# bh_carrier_0_beta.net
KiCad netlist of a schematic drawn in Altium Designer
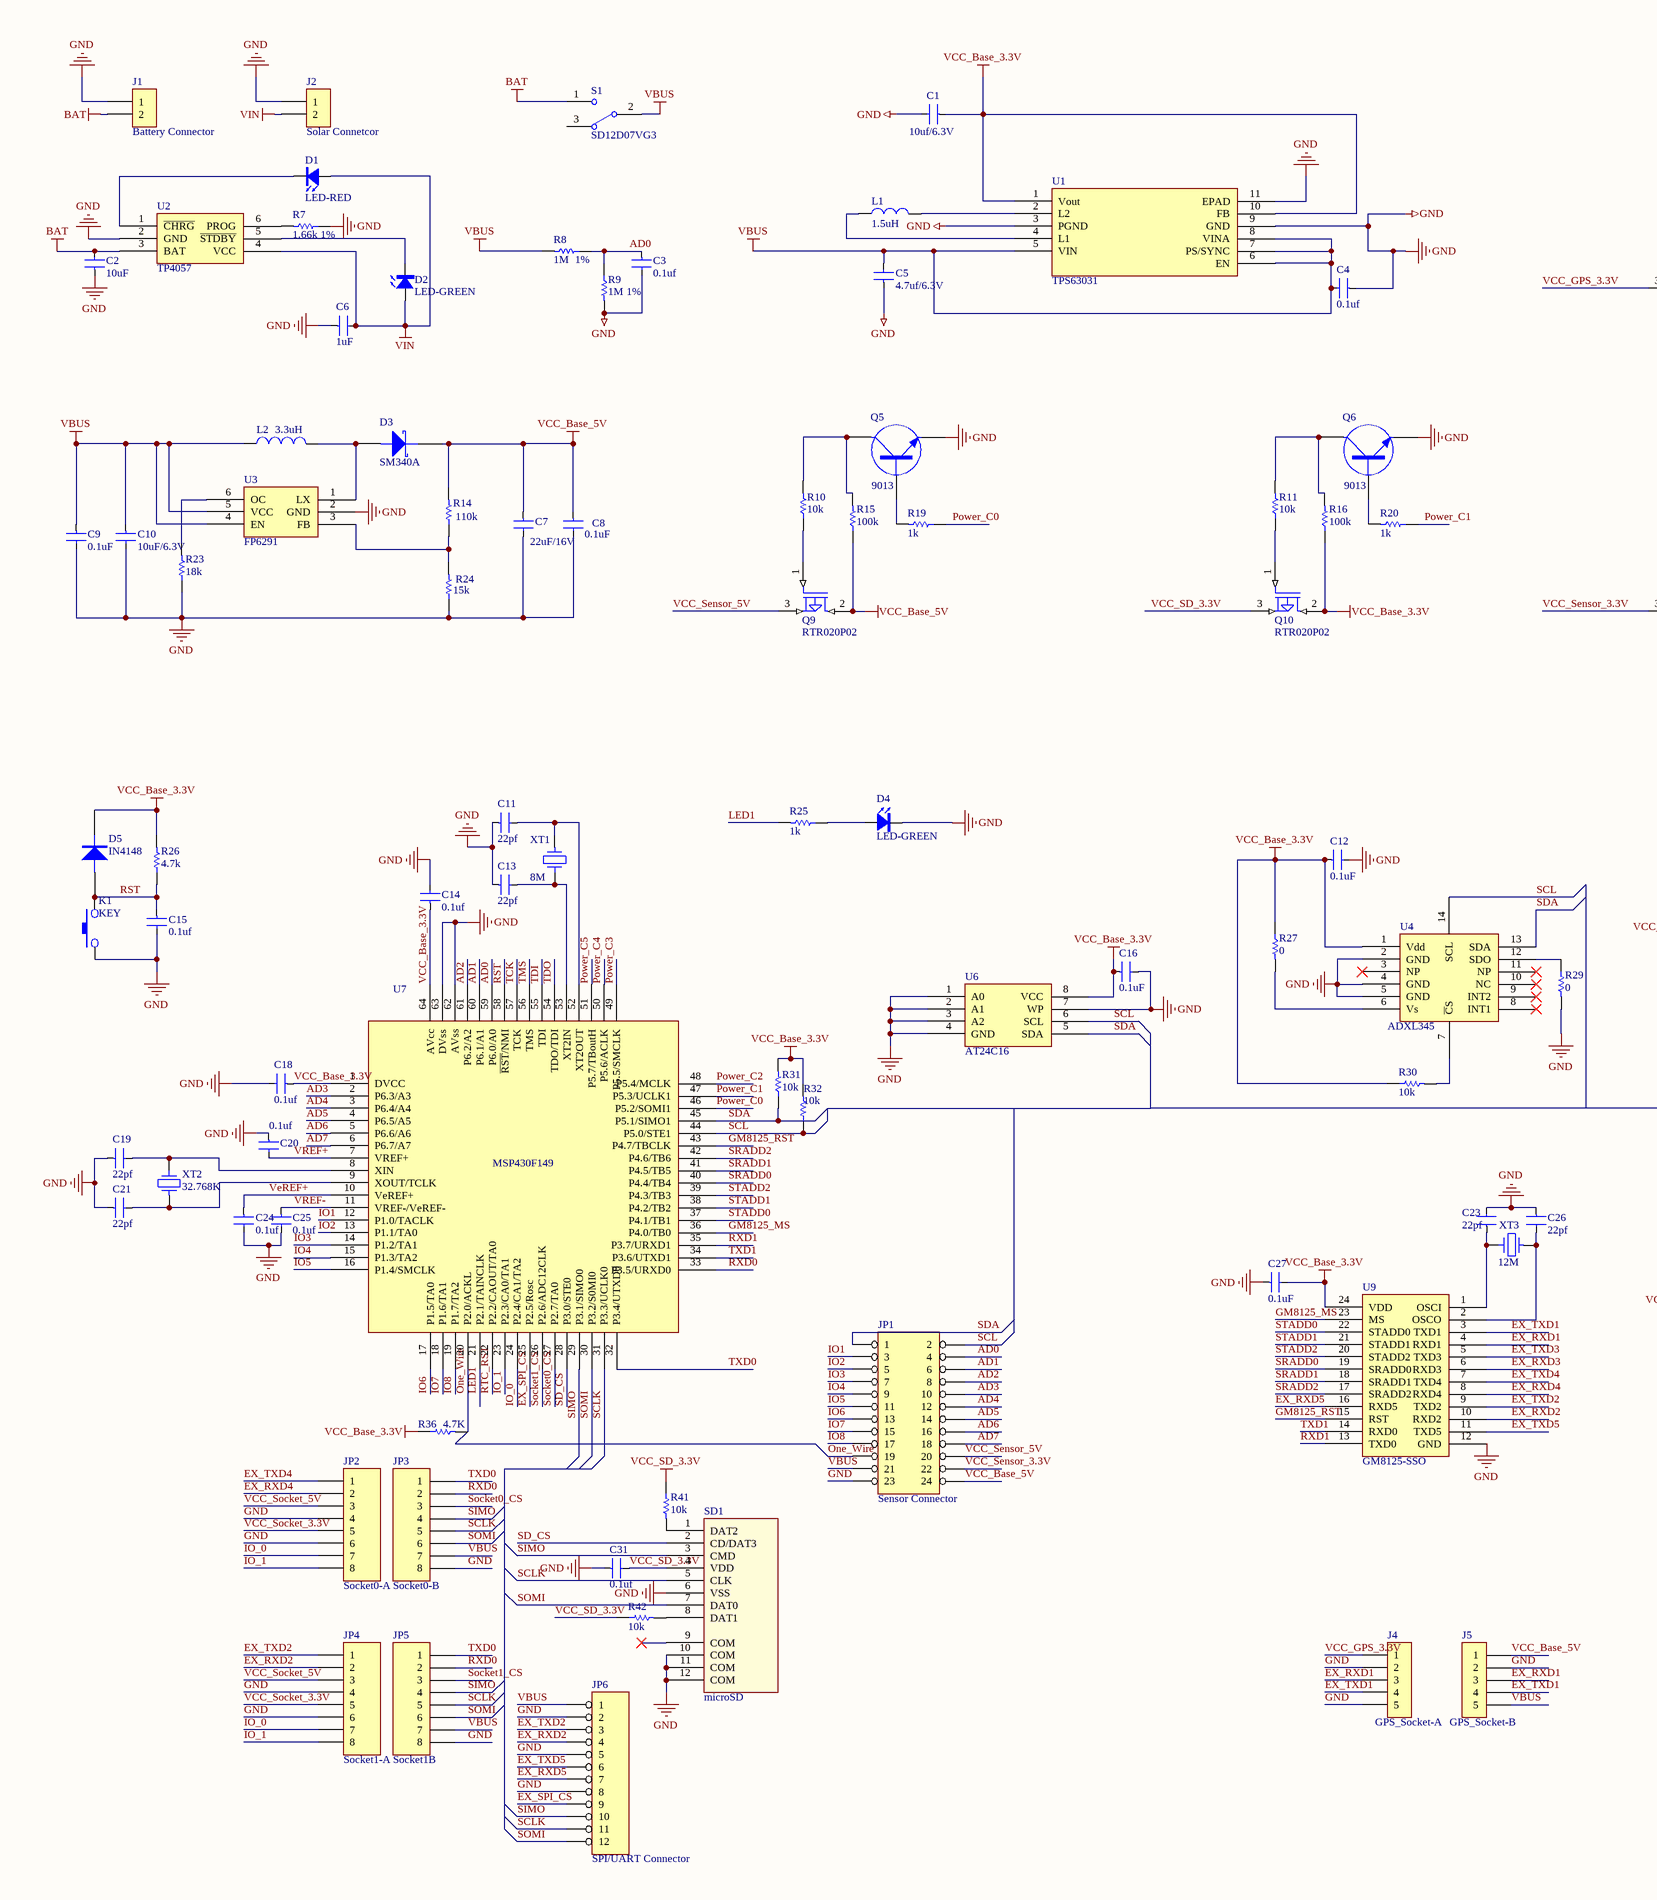
[diagram p0: bh_carrier_0_beta.SchDoc, left]
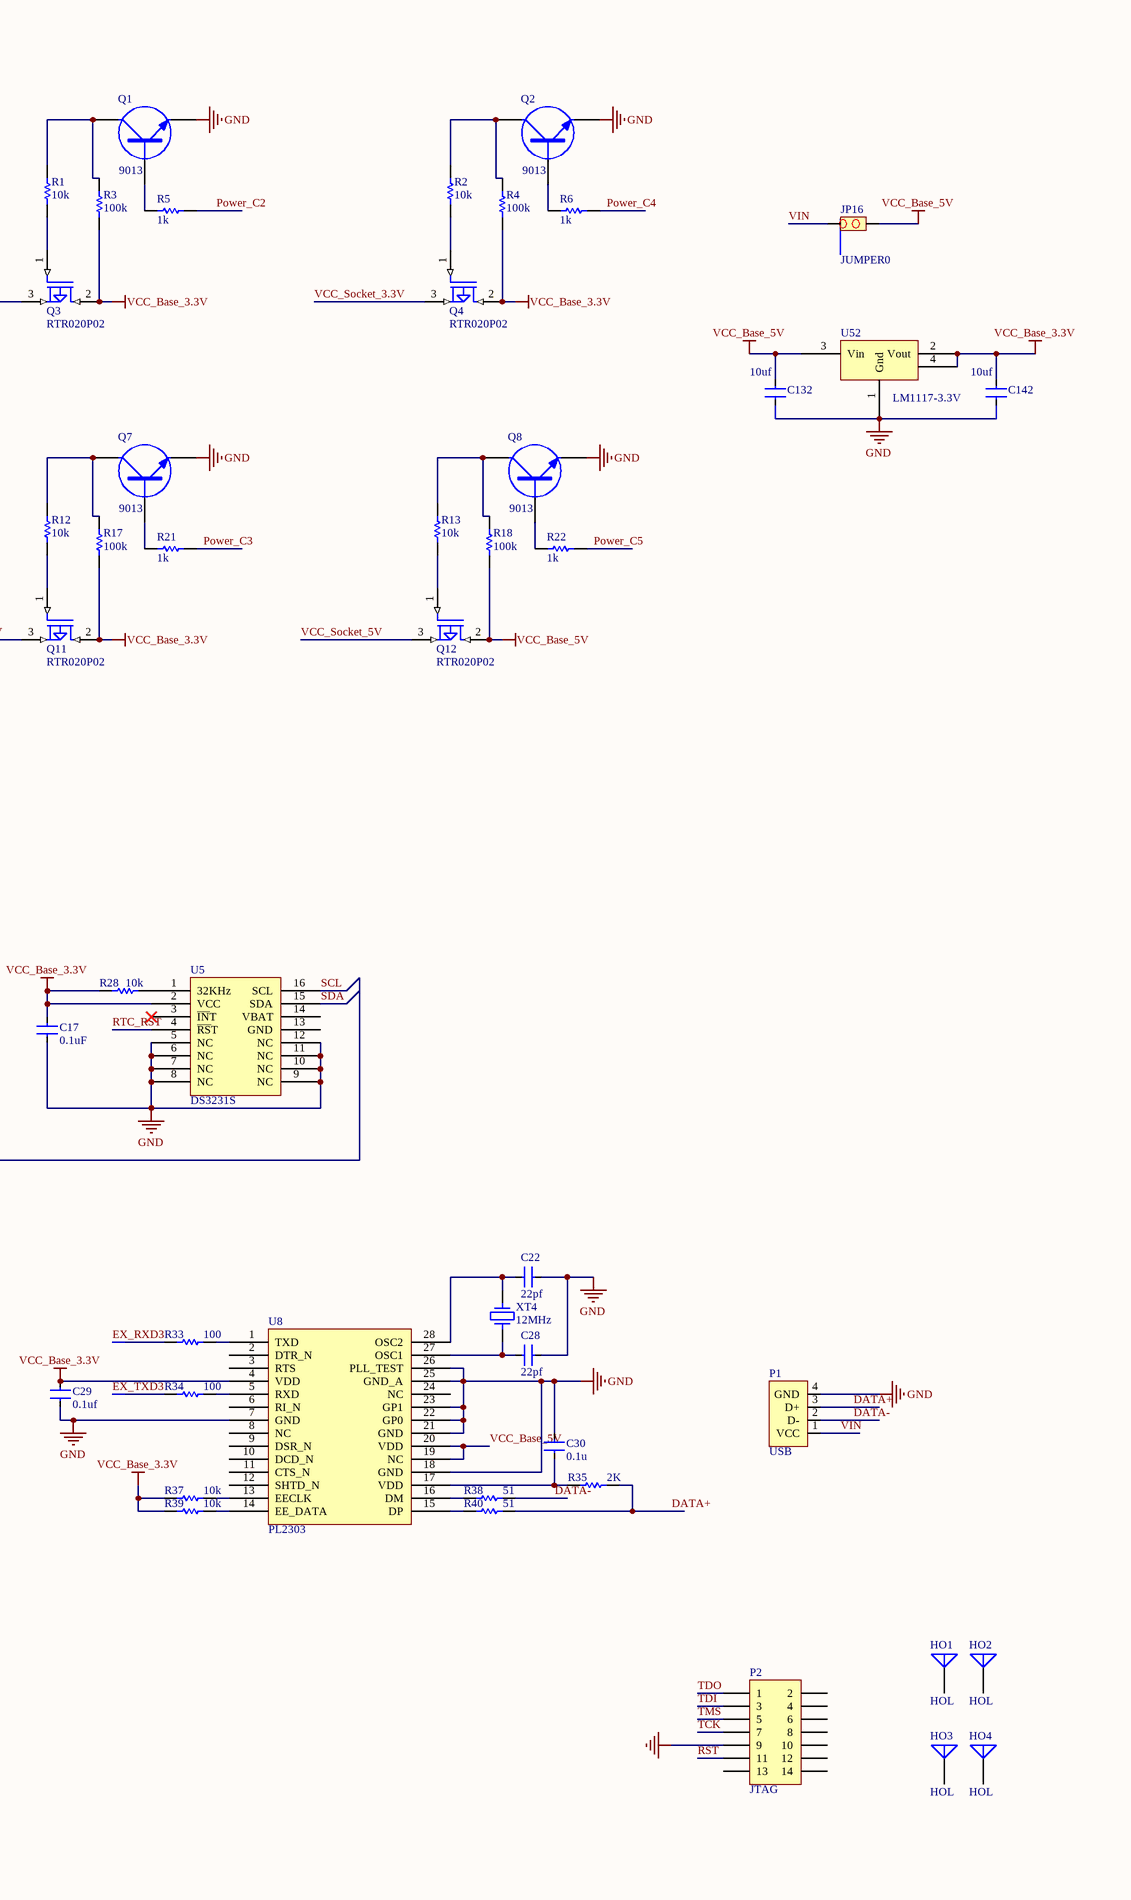
[diagram p1: bh_carrier_0_beta.SchDoc, right]

(export (version "E")
  (design (tool "Eeschema 10.0.6"))
  (components
    (comp (ref "C1")
      (value "10uf/6.3V")
      (footprint "C0603")
      (description "SMD-CAP")
      (libsource (lib "5D_USED_DEVICE") (part "CAP-SMD"))
    )
    (comp (ref "C2")
      (value "10uF")
      (footprint "C0603")
      (description "SMD-CAP")
      (libsource (lib "5D_DEVICE") (part "CAP-SMD"))
    )
    (comp (ref "C3")
      (value "0.1uf")
      (footprint "C0603")
      (description "SMD-CAP")
      (libsource (lib "5D_USED_DEVICE") (part "CAP-SMD"))
    )
    (comp (ref "C4")
      (value "0.1uf")
      (footprint "C0603")
      (description "SMD-CAP")
      (libsource (lib "5D_USED_DEVICE") (part "CAP-SMD"))
    )
    (comp (ref "C5")
      (value "4.7uf/6.3V")
      (footprint "C0603")
      (description "SMD-CAP")
      (libsource (lib "5D_USED_DEVICE") (part "CAP-SMD"))
    )
    (comp (ref "C6")
      (value "1uF")
      (footprint "C0603")
      (description "SMD-CAP")
      (libsource (lib "5D_DEVICE") (part "CAP-SMD"))
    )
    (comp (ref "C7")
      (value "22uF/16V")
      (footprint "C0603")
      (description "SMD-CAP")
      (libsource (lib "5D_DEVICE") (part "CAP-SMD"))
    )
    (comp (ref "C8")
      (value "0.1uF")
      (footprint "C0603")
      (description "SMD-CAP")
      (libsource (lib "5D_DEVICE") (part "CAP-SMD"))
    )
    (comp (ref "C9")
      (value "0.1uF")
      (footprint "C0603")
      (description "SMD-CAP")
      (libsource (lib "5D_DEVICE") (part "CAP-SMD"))
    )
    (comp (ref "C10")
      (value "10uF/6.3V")
      (footprint "C0603")
      (description "SMD-CAP")
      (libsource (lib "5D_DEVICE") (part "CAP-SMD"))
    )
    (comp (ref "C11")
      (value "22pf")
      (footprint "C0603")
      (description "SMD-CAP")
      (libsource (lib "5D_USED_DEVICE") (part "CAP-SMD"))
    )
    (comp (ref "C12")
      (value "0.1uF")
      (footprint "C0603")
      (description "SMD-CAP")
      (libsource (lib "5D_DEVICE") (part "CAP-SMD"))
    )
    (comp (ref "C13")
      (value "22pf")
      (footprint "C0603")
      (description "SMD-CAP")
      (libsource (lib "5D_USED_DEVICE") (part "CAP-SMD"))
    )
    (comp (ref "C14")
      (value "0.1uf")
      (footprint "C0603")
      (description "SMD-CAP")
      (libsource (lib "5D_USED_DEVICE") (part "CAP-SMD"))
    )
    (comp (ref "C15")
      (value "0.1uf")
      (footprint "C0603")
      (description "SMD-CAP")
      (libsource (lib "5D_USED_DEVICE") (part "CAP-SMD"))
    )
    (comp (ref "C16")
      (value "0.1uF")
      (footprint "C0603")
      (description "SMD-CAP")
      (libsource (lib "5D_DEVICE") (part "CAP-SMD"))
    )
    (comp (ref "C17")
      (value "0.1uF")
      (footprint "C0603")
      (description "SMD-CAP")
      (libsource (lib "5D_DEVICE") (part "CAP-SMD"))
    )
    (comp (ref "C18")
      (value "0.1uf")
      (footprint "C0603")
      (description "SMD-CAP")
      (libsource (lib "5D_USED_DEVICE") (part "CAP-SMD"))
    )
    (comp (ref "C19")
      (value "22pf")
      (footprint "C0603")
      (description "SMD-CAP")
      (libsource (lib "5D_USED_DEVICE") (part "CAP-SMD"))
    )
    (comp (ref "C20")
      (value "0.1uf")
      (footprint "C0603")
      (description "SMD-CAP")
      (libsource (lib "5D_USED_DEVICE") (part "CAP-SMD"))
    )
    (comp (ref "C21")
      (value "22pf")
      (footprint "C0603")
      (description "SMD-CAP")
      (libsource (lib "5D_USED_DEVICE") (part "CAP-SMD"))
    )
    (comp (ref "C22")
      (value "22pf")
      (footprint "C0603")
      (description "SMD-CAP")
      (libsource (lib "5D_USED_DEVICE") (part "CAP-SMD"))
    )
    (comp (ref "C23")
      (value "22pf")
      (footprint "C0603")
      (description "SMD-CAP")
      (libsource (lib "5D_USED_DEVICE") (part "CAP-SMD"))
    )
    (comp (ref "C24")
      (value "0.1uf")
      (footprint "C0603")
      (description "SMD-CAP")
      (libsource (lib "5D_USED_DEVICE") (part "CAP-SMD"))
    )
    (comp (ref "C25")
      (value "0.1uf")
      (footprint "C0603")
      (description "SMD-CAP")
      (libsource (lib "5D_USED_DEVICE") (part "CAP-SMD"))
    )
    (comp (ref "C26")
      (value "22pf")
      (footprint "C0603")
      (description "SMD-CAP")
      (libsource (lib "5D_USED_DEVICE") (part "CAP-SMD"))
    )
    (comp (ref "C27")
      (value "0.1uF")
      (footprint "C0603")
      (description "SMD-CAP")
      (libsource (lib "5D_DEVICE") (part "CAP-SMD"))
    )
    (comp (ref "C28")
      (value "22pf")
      (footprint "C0603")
      (description "SMD-CAP")
      (libsource (lib "5D_USED_DEVICE") (part "CAP-SMD"))
    )
    (comp (ref "C29")
      (value "0.1uf")
      (footprint "C0603")
      (description "SMD-CAP")
      (libsource (lib "5D_USED_DEVICE") (part "CAP-SMD"))
    )
    (comp (ref "C30")
      (value "0.1u")
      (footprint "C0603")
      (description "SMD-CAP")
      (libsource (lib "5D_USED_DEVICE") (part "CAP-SMD"))
    )
    (comp (ref "C31")
      (value "0.1uf")
      (footprint "C0603")
      (description "SMD-CAP")
      (libsource (lib "5D_USED_DEVICE") (part "CAP-SMD"))
    )
    (comp (ref "C132")
      (value "10uf")
      (footprint "C0603")
      (description "SMD-CAP")
      (libsource (lib "5D_USED_DEVICE") (part "CAP-SMD"))
    )
    (comp (ref "C142")
      (value "10uf")
      (footprint "C0603")
      (description "SMD-CAP")
      (libsource (lib "5D_USED_DEVICE") (part "CAP-SMD"))
    )
    (comp (ref "D1") (value "LED-RED") (footprint "D0805") (libsource (lib "5D_DEVICE") (part "LED")))
    (comp (ref "D2") (value "LED-GREEN") (footprint "D0805") (libsource (lib "") (part "LED_1")))
    (comp (ref "D3")
      (value "SM340A")
      (footprint "DO-214")
      (description "Schottky Diode")
      (libsource (lib "5D_DEVICE") (part "DIODE SCHOTTKY"))
    )
    (comp (ref "D4") (value "LED-GREEN") (footprint "D0805") (libsource (lib "") (part "LED_2")))
    (comp (ref "D5") (value "IN4148") (footprint "D1206") (libsource (lib "BH_DESIGN_DEVICE") (part "DIODE")))
    (comp (ref "HO1")
      (value "HOL")
      (footprint "HOLE1")
      (description "Generic Antenna")
      (fields (field (name "PUBLISHER") "Altium Limited"))
      (libsource (lib "Miscellaneous Devices") (part "Antenna"))
    )
    (comp (ref "HO2")
      (value "HOL")
      (footprint "HOLE1")
      (description "Generic Antenna")
      (fields (field (name "PUBLISHER") "Altium Limited"))
      (libsource (lib "Miscellaneous Devices") (part "Antenna"))
    )
    (comp (ref "HO3")
      (value "HOL")
      (footprint "HOLE1")
      (description "Generic Antenna")
      (fields (field (name "PUBLISHER") "Altium Limited"))
      (libsource (lib "Miscellaneous Devices") (part "Antenna"))
    )
    (comp (ref "HO4")
      (value "HOL")
      (footprint "HOLE1")
      (description "Generic Antenna")
      (fields (field (name "PUBLISHER") "Altium Limited"))
      (libsource (lib "Miscellaneous Devices") (part "Antenna"))
    )
    (comp (ref "J1")
      (value "Battery Connector")
      (footprint "SIP1X2X2.0")
      (description "Connector")
      (libsource (lib "5D_CONNECTOR") (part "SIP1X2"))
    )
    (comp (ref "J2")
      (value "Solar Connetcor")
      (footprint "SIP1X2X2.0")
      (description "Connector")
      (libsource (lib "5D_CONNECTOR") (part "SIP1X2"))
    )
    (comp (ref "J4")
      (value "GPS_Socket-A")
      (footprint "SIP1X5X2.54")
      (description "Connector")
      (libsource (lib "") (part "SIP1X5_1"))
    )
    (comp (ref "J5")
      (value "GPS_Socket-B")
      (footprint "SIP1X5X2.54")
      (description "Connector")
      (libsource (lib "5D_CONNECTOR") (part "SIP1X5"))
    )
    (comp (ref "JP1")
      (value "Sensor Connector")
      (footprint "SIP2X12X2.54")
      (libsource (lib "5D_CONNECTOR") (part "SIP2X12"))
    )
    (comp (ref "JP2")
      (value "Socket0-A")
      (footprint "SIP1x8x2.54")
      (description "8 Pin Header")
      (libsource (lib "5D_CONNECTOR") (part "SIP1X8"))
    )
    (comp (ref "JP3")
      (value "Socket0-B")
      (footprint "SIP1x8x2.54")
      (description "8 Pin Header")
      (libsource (lib "") (part "SIP1X8_1"))
    )
    (comp (ref "JP4")
      (value "Socket1-A")
      (footprint "SIP1x8x2.0")
      (description "8 Pin Header")
      (libsource (lib "5D_CONNECTOR") (part "SIP1X8"))
    )
    (comp (ref "JP5")
      (value "Socket1B")
      (footprint "SIP1x8x2.0")
      (description "8 Pin Header")
      (libsource (lib "") (part "SIP1X8_1"))
    )
    (comp (ref "JP6")
      (value "SPI/UART Connector")
      (footprint "SIP1x12x2.54")
      (description "12 Pin Header")
      (libsource (lib "5D_CONNECTOR") (part "SIP1X12"))
    )
    (comp (ref "JP16")
      (value "JUMPER0")
      (footprint "SIP1X2X2.54")
      (libsource (lib "BH_DESIGN_CONNECTOR") (part "JUMPER0"))
    )
    (comp (ref "K1") (value "KEY") (footprint "KEY_2Pin") (libsource (lib "5D_USED_DEVICE") (part "KEY")))
    (comp (ref "L1")
      (value "1.5uH")
      (footprint "LPS3010")
      (description "LPS3015-152")
      (libsource (lib "5D_DEVICE") (part "L1"))
    )
    (comp (ref "L2")
      (value "3.3uH")
      (footprint "L1206")
      (description "Inductor")
      (libsource (lib "5D_DEVICE") (part "INDUCTOR"))
    )
    (comp (ref "P1") (value "USB") (footprint "MicroUSB_four") (libsource (lib "5D_DEVICE") (part "USB")))
    (comp (ref "P2")
      (value "JTAG")
      (footprint "SIP2X7X2.54")
      (description "Header, 7-Pin, Dual row")
      (fields (field (name "PUBLISHER") "Altium Limited"))
      (libsource (lib "Miscellaneous Connectors") (part "Header 7X2"))
    )
    (comp (ref "Q1")
      (value "9013")
      (footprint "SOT-23")
      (description "NPN Transistor")
      (libsource (lib "5D_DEVICE") (part "NPN"))
    )
    (comp (ref "Q2")
      (value "9013")
      (footprint "SOT-23")
      (description "NPN Transistor")
      (libsource (lib "5D_DEVICE") (part "NPN"))
    )
    (comp (ref "Q3") (value "RTR020P02") (footprint "TSMT3") (libsource (lib "5D_DEVICE") (part "MOSFET P")))
    (comp (ref "Q4") (value "RTR020P02") (footprint "TSMT3") (libsource (lib "5D_DEVICE") (part "MOSFET P")))
    (comp (ref "Q5")
      (value "9013")
      (footprint "SOT-23")
      (description "NPN Transistor")
      (libsource (lib "5D_DEVICE") (part "NPN"))
    )
    (comp (ref "Q6")
      (value "9013")
      (footprint "SOT-23")
      (description "NPN Transistor")
      (libsource (lib "5D_DEVICE") (part "NPN"))
    )
    (comp (ref "Q7")
      (value "9013")
      (footprint "SOT-23")
      (description "NPN Transistor")
      (libsource (lib "5D_DEVICE") (part "NPN"))
    )
    (comp (ref "Q8")
      (value "9013")
      (footprint "SOT-23")
      (description "NPN Transistor")
      (libsource (lib "5D_DEVICE") (part "NPN"))
    )
    (comp (ref "Q9") (value "RTR020P02") (footprint "TSMT3") (libsource (lib "5D_DEVICE") (part "MOSFET P")))
    (comp (ref "Q10") (value "RTR020P02") (footprint "TSMT3") (libsource (lib "5D_DEVICE") (part "MOSFET P")))
    (comp (ref "Q11") (value "RTR020P02") (footprint "TSMT3") (libsource (lib "5D_DEVICE") (part "MOSFET P")))
    (comp (ref "Q12") (value "RTR020P02") (footprint "TSMT3") (libsource (lib "5D_DEVICE") (part "MOSFET P")))
    (comp (ref "R1")
      (value "10k")
      (footprint "R0603")
      (description "Resistor")
      (libsource (lib "5D_DEVICE") (part "RES"))
    )
    (comp (ref "R2")
      (value "10k")
      (footprint "R0603")
      (description "Resistor")
      (libsource (lib "5D_DEVICE") (part "RES"))
    )
    (comp (ref "R3")
      (value "100k")
      (footprint "R0603")
      (description "Resistor")
      (libsource (lib "5D_DEVICE") (part "RES"))
    )
    (comp (ref "R4")
      (value "100k")
      (footprint "R0603")
      (description "Resistor")
      (libsource (lib "5D_DEVICE") (part "RES"))
    )
    (comp (ref "R5")
      (value "1k")
      (footprint "R0603")
      (description "Resistor")
      (libsource (lib "5D_DEVICE") (part "RES"))
    )
    (comp (ref "R6")
      (value "1k")
      (footprint "R0603")
      (description "Resistor")
      (libsource (lib "5D_DEVICE") (part "RES"))
    )
    (comp (ref "R7")
      (value "1.66k 1%")
      (footprint "R0603")
      (description "Resistor")
      (libsource (lib "5D_DEVICE") (part "RES"))
    )
    (comp (ref "R8")
      (value "1M  1%")
      (footprint "R0603")
      (description "Resistor")
      (libsource (lib "5D_DEVICE") (part "RES"))
    )
    (comp (ref "R9")
      (value "1M 1%")
      (footprint "R0603")
      (description "Resistor")
      (libsource (lib "5D_DEVICE") (part "RES"))
    )
    (comp (ref "R10")
      (value "10k")
      (footprint "R0603")
      (description "Resistor")
      (libsource (lib "5D_DEVICE") (part "RES"))
    )
    (comp (ref "R11")
      (value "10k")
      (footprint "R0603")
      (description "Resistor")
      (libsource (lib "5D_DEVICE") (part "RES"))
    )
    (comp (ref "R12")
      (value "10k")
      (footprint "R0603")
      (description "Resistor")
      (libsource (lib "5D_DEVICE") (part "RES"))
    )
    (comp (ref "R13")
      (value "10k")
      (footprint "R0603")
      (description "Resistor")
      (libsource (lib "5D_DEVICE") (part "RES"))
    )
    (comp (ref "R14")
      (value "110k")
      (footprint "R0603")
      (description "Resistor")
      (libsource (lib "5D_DEVICE") (part "RES"))
    )
    (comp (ref "R15")
      (value "100k")
      (footprint "R0603")
      (description "Resistor")
      (libsource (lib "5D_DEVICE") (part "RES"))
    )
    (comp (ref "R16")
      (value "100k")
      (footprint "R0603")
      (description "Resistor")
      (libsource (lib "5D_DEVICE") (part "RES"))
    )
    (comp (ref "R17")
      (value "100k")
      (footprint "R0603")
      (description "Resistor")
      (libsource (lib "5D_DEVICE") (part "RES"))
    )
    (comp (ref "R18")
      (value "100k")
      (footprint "R0603")
      (description "Resistor")
      (libsource (lib "5D_DEVICE") (part "RES"))
    )
    (comp (ref "R19")
      (value "1k")
      (footprint "R0603")
      (description "Resistor")
      (libsource (lib "5D_DEVICE") (part "RES"))
    )
    (comp (ref "R20")
      (value "1k")
      (footprint "R0603")
      (description "Resistor")
      (libsource (lib "5D_DEVICE") (part "RES"))
    )
    (comp (ref "R21")
      (value "1k")
      (footprint "R0603")
      (description "Resistor")
      (libsource (lib "5D_DEVICE") (part "RES"))
    )
    (comp (ref "R22")
      (value "1k")
      (footprint "R0603")
      (description "Resistor")
      (libsource (lib "5D_DEVICE") (part "RES"))
    )
    (comp (ref "R23")
      (value "18k")
      (footprint "R0603")
      (description "Resistor")
      (libsource (lib "5D_DEVICE") (part "RES"))
    )
    (comp (ref "R24")
      (value "15k")
      (footprint "R0603")
      (description "Resistor")
      (libsource (lib "5D_DEVICE") (part "RES"))
    )
    (comp (ref "R25")
      (value "1k")
      (footprint "R0603")
      (description "Resistor")
      (libsource (lib "5D_DEVICE") (part "RES"))
    )
    (comp (ref "R26")
      (value "4.7k")
      (footprint "R0603")
      (description "Resistor")
      (libsource (lib "5D_DEVICE") (part "RES"))
    )
    (comp (ref "R27")
      (value "0")
      (footprint "R0603")
      (description "Resistor")
      (libsource (lib "5D_DEVICE") (part "RES"))
    )
    (comp (ref "R28")
      (value "10k")
      (footprint "R0603")
      (description "Resistor")
      (libsource (lib "5D_DEVICE") (part "RES"))
    )
    (comp (ref "R29")
      (value "0")
      (footprint "R0603")
      (description "Resistor")
      (libsource (lib "5D_DEVICE") (part "RES"))
    )
    (comp (ref "R30")
      (value "10k")
      (footprint "R0603")
      (description "Resistor")
      (libsource (lib "5D_DEVICE") (part "RES"))
    )
    (comp (ref "R31")
      (value "10k")
      (footprint "R0603")
      (description "Resistor")
      (libsource (lib "5D_DEVICE") (part "RES"))
    )
    (comp (ref "R32")
      (value "10k")
      (footprint "R0603")
      (description "Resistor")
      (libsource (lib "5D_DEVICE") (part "RES"))
    )
    (comp (ref "R33")
      (value "100")
      (footprint "R0603")
      (description "Resistor")
      (libsource (lib "5D_DEVICE") (part "RES"))
    )
    (comp (ref "R34")
      (value "100")
      (footprint "R0603")
      (description "Resistor")
      (libsource (lib "5D_DEVICE") (part "RES"))
    )
    (comp (ref "R35")
      (value "2K")
      (footprint "R0603")
      (description "Resistor")
      (fields (field (name "Comment") "2k"))
      (libsource (lib "5D_DEVICE") (part "RES"))
    )
    (comp (ref "R36")
      (value "4.7K")
      (footprint "R0603")
      (description "Resistor")
      (libsource (lib "5D_DEVICE") (part "RES"))
    )
    (comp (ref "R37")
      (value "10k")
      (footprint "R0603")
      (description "Resistor")
      (libsource (lib "5D_DEVICE") (part "RES"))
    )
    (comp (ref "R38")
      (value "51")
      (footprint "R0603")
      (description "Resistor")
      (libsource (lib "5D_DEVICE") (part "RES"))
    )
    (comp (ref "R39")
      (value "10k")
      (footprint "R0603")
      (description "Resistor")
      (libsource (lib "5D_DEVICE") (part "RES"))
    )
    (comp (ref "R40")
      (value "51")
      (footprint "R0603")
      (description "Resistor")
      (libsource (lib "5D_DEVICE") (part "RES"))
    )
    (comp (ref "R41")
      (value "10k")
      (footprint "R0603")
      (description "Resistor")
      (libsource (lib "5D_DEVICE") (part "RES"))
    )
    (comp (ref "R42")
      (value "10k")
      (footprint "R0603")
      (description "Resistor")
      (libsource (lib "5D_DEVICE") (part "RES"))
    )
    (comp (ref "S1")
      (value "SD12D07VG3")
      (footprint "SW-1-2")
      (fields (field (name "PUBLISHER") "Altium Limited"))
      (libsource (lib "Miscellaneous Devices") (part "SW-SPDT"))
    )
    (comp (ref "SD1") (value "microSD") (footprint "TF_CARD") (libsource (lib "tlib") (part "microSD")))
    (comp (ref "U1") (value "TPS63031") (footprint "QFN-10") (libsource (lib "5D_IC") (part "TPS63031_2")))
    (comp (ref "U2") (value "TP4057") (footprint "SOT23-6") (libsource (lib "5D_DEVICE") (part "PT4057")))
    (comp (ref "U3") (value "FP6291") (footprint "SOT23-6") (libsource (lib "5D_IC") (part "FP6291")))
    (comp (ref "U4") (value "ADXL345") (footprint "LGA-CC-14-1") (libsource (lib "5D_IC") (part "ADXL345")))
    (comp (ref "U5") (value "DS3231S") (footprint "SOP16") (libsource (lib "5D_IC") (part "DS3231")))
    (comp (ref "U6") (value "AT24C16") (footprint "SO-8") (libsource (lib "5D_IC") (part "AT24C16")))
    (comp (ref "U7")
      (value "MSP430F149")
      (footprint "LQFP64_M")
      (libsource (lib "Schlib1") (part "MSP430F149"))
    )
    (comp (ref "U8") (value "PL2303") (footprint "SOP28") (libsource (lib "Schlib1") (part "PL2303")))
    (comp (ref "U9") (value "GM8125-SSO") (footprint "SOP-24") (libsource (lib "5D_IC") (part "GM8125")))
    (comp (ref "U52")
      (value "LM1117-3.3V")
      (footprint "SOT-223")
      (description "ASM1117-2.5V")
      (libsource (lib "5D_USED_DEVICE") (part "ASM1117-2.5V"))
    )
    (comp (ref "XT1")
      (value "8M")
      (footprint "HC-49S")
      (description "晶振")
      (libsource (lib "5D_USED_DEVICE") (part "XT"))
    )
    (comp (ref "XT2")
      (value "32.768K")
      (footprint "AT308")
      (description "晶振")
      (libsource (lib "5D_USED_DEVICE") (part "XT"))
    )
    (comp (ref "XT3")
      (value "12M")
      (footprint "HC-49S")
      (description "晶振")
      (libsource (lib "5D_USED_DEVICE") (part "XT"))
    )
    (comp (ref "XT4")
      (value "12MHz")
      (footprint "HC-49S")
      (description "晶振")
      (libsource (lib "5D_USED_DEVICE") (part "XT"))
    )
  )
  (nets
    (net (code "1") (name "/AD0") (class "Default")
      (node (ref "C3") (pin "1") (pinfunction "1_1") (pintype "passive"))
      (node (ref "JP1") (pin "4") (pinfunction "4_4") (pintype "passive"))
      (node (ref "R8") (pin "1") (pinfunction "1_1") (pintype "passive"))
      (node (ref "R9") (pin "1") (pinfunction "1_1") (pintype "passive"))
      (node (ref "U7") (pin "59") (pinfunction "P6.0/A0_59") (pintype "passive"))
    )
    (net (code "2") (name "/AD1") (class "Default")
      (node (ref "JP1") (pin "6") (pinfunction "6_6") (pintype "passive"))
      (node (ref "U7") (pin "60") (pinfunction "P6.1/A1_60") (pintype "passive"))
    )
    (net (code "3") (name "/AD2") (class "Default")
      (node (ref "JP1") (pin "8") (pinfunction "8_8") (pintype "passive"))
      (node (ref "U7") (pin "61") (pinfunction "P6.2/A2_61") (pintype "passive"))
    )
    (net (code "4") (name "/AD3") (class "Default")
      (node (ref "JP1") (pin "10") (pinfunction "10_10") (pintype "passive"))
      (node (ref "U7") (pin "2") (pinfunction "P6.3/A3_2") (pintype "passive"))
    )
    (net (code "5") (name "/AD4") (class "Default")
      (node (ref "JP1") (pin "12") (pinfunction "12_12") (pintype "passive"))
      (node (ref "U7") (pin "3") (pinfunction "P6.4/A4_3") (pintype "passive"))
    )
    (net (code "6") (name "/AD5") (class "Default")
      (node (ref "JP1") (pin "14") (pinfunction "14_14") (pintype "passive"))
      (node (ref "U7") (pin "4") (pinfunction "P6.5/A5_4") (pintype "passive"))
    )
    (net (code "7") (name "/AD6") (class "Default")
      (node (ref "JP1") (pin "16") (pinfunction "16_16") (pintype "passive"))
      (node (ref "U7") (pin "5") (pinfunction "P6.6/A6_5") (pintype "passive"))
    )
    (net (code "8") (name "/AD7") (class "Default")
      (node (ref "JP1") (pin "18") (pinfunction "18_18") (pintype "passive"))
      (node (ref "U7") (pin "6") (pinfunction "P6.7/A7_6") (pintype "passive"))
    )
    (net (code "9") (name "/DATA+") (class "Default")
      (node (ref "P1") (pin "3") (pinfunction "D+_3") (pintype "passive"))
      (node (ref "R35") (pin "1") (pinfunction "1_1") (pintype "passive"))
      (node (ref "R40") (pin "1") (pinfunction "1_1") (pintype "passive"))
    )
    (net (code "10") (name "/DATA-") (class "Default")
      (node (ref "P1") (pin "2") (pinfunction "D-_2") (pintype "passive"))
      (node (ref "R38") (pin "1") (pinfunction "1_1") (pintype "passive"))
    )
    (net (code "11") (name "/EX_RXD1") (class "Default")
      (node (ref "J4") (pin "3") (pinfunction "3_3") (pintype "passive"))
      (node (ref "J5") (pin "3") (pinfunction "3_3") (pintype "passive"))
      (node (ref "U9") (pin "4") (pinfunction "RXD1_4") (pintype "passive"))
    )
    (net (code "12") (name "/EX_RXD2") (class "Default")
      (node (ref "JP4") (pin "2") (pinfunction "2_2") (pintype "passive"))
      (node (ref "JP6") (pin "4") (pinfunction "4_4") (pintype "passive"))
      (node (ref "U9") (pin "10") (pinfunction "RXD2_10") (pintype "passive"))
    )
    (net (code "13") (name "/EX_RXD3") (class "Default")
      (node (ref "R33") (pin "2") (pinfunction "2_2") (pintype "passive"))
      (node (ref "U9") (pin "6") (pinfunction "RXD3_6") (pintype "passive"))
    )
    (net (code "14") (name "/EX_RXD4") (class "Default")
      (node (ref "JP2") (pin "2") (pinfunction "2_2") (pintype "passive"))
      (node (ref "U9") (pin "8") (pinfunction "RXD4_8") (pintype "passive"))
    )
    (net (code "15") (name "/EX_RXD5") (class "Default")
      (node (ref "JP6") (pin "7") (pinfunction "7_7") (pintype "passive"))
      (node (ref "U9") (pin "16") (pinfunction "RXD5_16") (pintype "passive"))
    )
    (net (code "16") (name "/EX_SPI_CS") (class "Default")
      (node (ref "JP6") (pin "9") (pinfunction "9_9") (pintype "passive"))
      (node (ref "U7") (pin "25") (pinfunction "P2.5/Rosc_25") (pintype "passive"))
    )
    (net (code "17") (name "/EX_TXD1") (class "Default")
      (node (ref "J4") (pin "4") (pinfunction "4_4") (pintype "passive"))
      (node (ref "J5") (pin "4") (pinfunction "4_4") (pintype "passive"))
      (node (ref "U9") (pin "3") (pinfunction "TXD1_3") (pintype "passive"))
    )
    (net (code "18") (name "/EX_TXD2") (class "Default")
      (node (ref "JP4") (pin "1") (pinfunction "1_1") (pintype "passive"))
      (node (ref "JP6") (pin "3") (pinfunction "3_3") (pintype "passive"))
      (node (ref "U9") (pin "9") (pinfunction "TXD2_9") (pintype "passive"))
    )
    (net (code "19") (name "/EX_TXD3") (class "Default")
      (node (ref "R34") (pin "2") (pinfunction "2_2") (pintype "passive"))
      (node (ref "U9") (pin "5") (pinfunction "TXD3_5") (pintype "passive"))
    )
    (net (code "20") (name "/EX_TXD4") (class "Default")
      (node (ref "JP2") (pin "1") (pinfunction "1_1") (pintype "passive"))
      (node (ref "U9") (pin "7") (pinfunction "TXD4_7") (pintype "passive"))
    )
    (net (code "21") (name "/EX_TXD5") (class "Default")
      (node (ref "JP6") (pin "6") (pinfunction "6_6") (pintype "passive"))
      (node (ref "U9") (pin "11") (pinfunction "TXD5_11") (pintype "passive"))
    )
    (net (code "22") (name "/GM8125_MS") (class "Default")
      (node (ref "U7") (pin "36") (pinfunction "P4.0/TB0_36") (pintype "passive"))
      (node (ref "U9") (pin "23") (pinfunction "MS_23") (pintype "passive"))
    )
    (net (code "23") (name "/GM8125_RST") (class "Default")
      (node (ref "U7") (pin "43") (pinfunction "P4.7/TBCLK_43") (pintype "passive"))
      (node (ref "U9") (pin "15") (pinfunction "RST_15") (pintype "passive"))
    )
    (net (code "24") (name "/IO1") (class "Default")
      (node (ref "JP1") (pin "3") (pinfunction "3_3") (pintype "passive"))
      (node (ref "U7") (pin "12") (pinfunction "P1.0/TACLK_12") (pintype "passive"))
    )
    (net (code "25") (name "/IO2") (class "Default")
      (node (ref "JP1") (pin "5") (pinfunction "5_5") (pintype "passive"))
      (node (ref "U7") (pin "13") (pinfunction "P1.1/TA0_13") (pintype "passive"))
    )
    (net (code "26") (name "/IO3") (class "Default")
      (node (ref "JP1") (pin "7") (pinfunction "7_7") (pintype "passive"))
      (node (ref "U7") (pin "14") (pinfunction "P1.2/TA1_14") (pintype "passive"))
    )
    (net (code "27") (name "/IO4") (class "Default")
      (node (ref "JP1") (pin "9") (pinfunction "9_9") (pintype "passive"))
      (node (ref "U7") (pin "15") (pinfunction "P1.3/TA2_15") (pintype "passive"))
    )
    (net (code "28") (name "/IO5") (class "Default")
      (node (ref "JP1") (pin "11") (pinfunction "11_11") (pintype "passive"))
      (node (ref "U7") (pin "16") (pinfunction "P1.4/SMCLK_16") (pintype "passive"))
    )
    (net (code "29") (name "/IO6") (class "Default")
      (node (ref "JP1") (pin "13") (pinfunction "13_13") (pintype "passive"))
      (node (ref "U7") (pin "17") (pinfunction "P1.5/TA0_17") (pintype "passive"))
    )
    (net (code "30") (name "/IO7") (class "Default")
      (node (ref "JP1") (pin "15") (pinfunction "15_15") (pintype "passive"))
      (node (ref "U7") (pin "18") (pinfunction "P1.6/TA1_18") (pintype "passive"))
    )
    (net (code "31") (name "/IO8") (class "Default")
      (node (ref "JP1") (pin "17") (pinfunction "17_17") (pintype "passive"))
      (node (ref "U7") (pin "19") (pinfunction "P1.7/TA2_19") (pintype "passive"))
    )
    (net (code "32") (name "/IO_0") (class "Default")
      (node (ref "JP2") (pin "7") (pinfunction "7_7") (pintype "passive"))
      (node (ref "JP4") (pin "7") (pinfunction "7_7") (pintype "passive"))
      (node (ref "U7") (pin "24") (pinfunction "P2.4/CA1/TA2_24") (pintype "passive"))
    )
    (net (code "33") (name "/IO_1") (class "Default")
      (node (ref "JP2") (pin "8") (pinfunction "8_8") (pintype "passive"))
      (node (ref "JP4") (pin "8") (pinfunction "8_8") (pintype "passive"))
      (node (ref "U7") (pin "23") (pinfunction "P2.3/CA0/TA1_23") (pintype "passive"))
    )
    (net (code "34") (name "/LED1") (class "Default")
      (node (ref "R25") (pin "2") (pinfunction "2_2") (pintype "passive"))
      (node (ref "U7") (pin "21") (pinfunction "P2.1/TAINCLK_21") (pintype "passive"))
    )
    (net (code "35") (name "/One_Wire") (class "Default")
      (node (ref "JP1") (pin "19") (pinfunction "19_19") (pintype "passive"))
      (node (ref "R36") (pin "2") (pinfunction "2_2") (pintype "passive"))
      (node (ref "U7") (pin "20") (pinfunction "P2.0/ACKL_20") (pintype "passive"))
    )
    (net (code "36") (name "/Power_C0") (class "Default")
      (node (ref "R19") (pin "1") (pinfunction "1_1") (pintype "passive"))
      (node (ref "U7") (pin "46") (pinfunction "P5.2/SOMI1_46") (pintype "passive"))
    )
    (net (code "37") (name "/Power_C1") (class "Default")
      (node (ref "R20") (pin "1") (pinfunction "1_1") (pintype "passive"))
      (node (ref "U7") (pin "47") (pinfunction "P5.3/UCLK1_47") (pintype "passive"))
    )
    (net (code "38") (name "/Power_C2") (class "Default")
      (node (ref "R5") (pin "1") (pinfunction "1_1") (pintype "passive"))
      (node (ref "U7") (pin "48") (pinfunction "P5.4/MCLK_48") (pintype "passive"))
    )
    (net (code "39") (name "/Power_C3") (class "Default")
      (node (ref "R21") (pin "1") (pinfunction "1_1") (pintype "passive"))
      (node (ref "U7") (pin "49") (pinfunction "P5.5/SMCLK_49") (pintype "passive"))
    )
    (net (code "40") (name "/Power_C4") (class "Default")
      (node (ref "R6") (pin "1") (pinfunction "1_1") (pintype "passive"))
      (node (ref "U7") (pin "50") (pinfunction "P5.6/ACLK_50") (pintype "passive"))
    )
    (net (code "41") (name "/Power_C5") (class "Default")
      (node (ref "R22") (pin "1") (pinfunction "1_1") (pintype "passive"))
      (node (ref "U7") (pin "51") (pinfunction "P5.7/TBoutH_51") (pintype "passive"))
    )
    (net (code "42") (name "/RST") (class "Default")
      (node (ref "C15") (pin "1") (pinfunction "1_1") (pintype "passive"))
      (node (ref "D5") (pin "1") (pinfunction "A_1") (pintype "passive"))
      (node (ref "K1") (pin "2") (pinfunction "2_2") (pintype "passive"))
      (node (ref "P2") (pin "11") (pinfunction "11_11") (pintype "passive"))
      (node (ref "R26") (pin "1") (pinfunction "1_1") (pintype "passive"))
      (node (ref "U7") (pin "58") (pinfunction "~{RST}/NMI_58") (pintype "passive"))
    )
    (net (code "43") (name "/RTC_RST") (class "Default")
      (node (ref "U5") (pin "4") (pinfunction "~{RS}T_4") (pintype "passive"))
      (node (ref "U7") (pin "22") (pinfunction "P2.2/CAOUT/TA0_22") (pintype "passive"))
    )
    (net (code "44") (name "/RXD0") (class "Default")
      (node (ref "JP3") (pin "2") (pinfunction "2_2") (pintype "passive"))
      (node (ref "JP5") (pin "2") (pinfunction "2_2") (pintype "passive"))
      (node (ref "U7") (pin "33") (pinfunction "P3.5/URXD0_33") (pintype "passive"))
    )
    (net (code "45") (name "/RXD1") (class "Default")
      (node (ref "U7") (pin "35") (pinfunction "P3.7/URXD1_35") (pintype "passive"))
      (node (ref "U9") (pin "13") (pinfunction "TXD0_13") (pintype "passive"))
    )
    (net (code "46") (name "/SCL") (class "Default")
      (node (ref "JP1") (pin "2") (pinfunction "2_2") (pintype "passive"))
      (node (ref "R32") (pin "1") (pinfunction "1_1") (pintype "passive"))
      (node (ref "U4") (pin "14") (pinfunction "SCL_14") (pintype "passive"))
      (node (ref "U5") (pin "16") (pinfunction "SCL_16") (pintype "passive"))
      (node (ref "U6") (pin "6") (pinfunction "SCL_6") (pintype "passive"))
      (node (ref "U7") (pin "44") (pinfunction "P5.0/STE1_44") (pintype "passive"))
    )
    (net (code "47") (name "/SCLK") (class "Default")
      (node (ref "JP3") (pin "5") (pinfunction "5_5") (pintype "passive"))
      (node (ref "JP5") (pin "5") (pinfunction "5_5") (pintype "passive"))
      (node (ref "JP6") (pin "11") (pinfunction "11_11") (pintype "passive"))
      (node (ref "SD1") (pin "5") (pinfunction "CLK_5") (pintype "passive"))
      (node (ref "U7") (pin "31") (pinfunction "P3.3/UCLK0_31") (pintype "passive"))
    )
    (net (code "48") (name "/SDA") (class "Default")
      (node (ref "JP1") (pin "1") (pinfunction "1_1") (pintype "passive"))
      (node (ref "R31") (pin "1") (pinfunction "1_1") (pintype "passive"))
      (node (ref "U4") (pin "13") (pinfunction "SDA_13") (pintype "passive"))
      (node (ref "U5") (pin "15") (pinfunction "SDA_15") (pintype "passive"))
      (node (ref "U6") (pin "5") (pinfunction "SDA_5") (pintype "passive"))
      (node (ref "U7") (pin "45") (pinfunction "P5.1/SIMO1_45") (pintype "passive"))
    )
    (net (code "49") (name "/SD_CS") (class "Default")
      (node (ref "SD1") (pin "2") (pinfunction "CD/DAT3_2") (pintype "passive"))
      (node (ref "U7") (pin "28") (pinfunction "P3.0/STE0_28") (pintype "passive"))
    )
    (net (code "50") (name "/SIMO") (class "Default")
      (node (ref "JP3") (pin "4") (pinfunction "4_4") (pintype "passive"))
      (node (ref "JP5") (pin "4") (pinfunction "4_4") (pintype "passive"))
      (node (ref "JP6") (pin "10") (pinfunction "10_10") (pintype "passive"))
      (node (ref "SD1") (pin "3") (pinfunction "CMD_3") (pintype "passive"))
      (node (ref "U7") (pin "29") (pinfunction "P3.1/SIMO0_29") (pintype "passive"))
    )
    (net (code "51") (name "/SOMI") (class "Default")
      (node (ref "JP3") (pin "6") (pinfunction "6_6") (pintype "passive"))
      (node (ref "JP5") (pin "6") (pinfunction "6_6") (pintype "passive"))
      (node (ref "JP6") (pin "12") (pinfunction "12_12") (pintype "passive"))
      (node (ref "SD1") (pin "7") (pinfunction "DAT0_7") (pintype "passive"))
      (node (ref "U7") (pin "30") (pinfunction "P3.2/S0MI0_30") (pintype "passive"))
    )
    (net (code "52") (name "/SRADD0") (class "Default")
      (node (ref "U7") (pin "40") (pinfunction "P4.4/TB4_40") (pintype "passive"))
      (node (ref "U9") (pin "19") (pinfunction "SRADD0_19") (pintype "passive"))
    )
    (net (code "53") (name "/SRADD1") (class "Default")
      (node (ref "U7") (pin "41") (pinfunction "P4.5/TB5_41") (pintype "passive"))
      (node (ref "U9") (pin "18") (pinfunction "SRADD1_18") (pintype "passive"))
    )
    (net (code "54") (name "/SRADD2") (class "Default")
      (node (ref "U7") (pin "42") (pinfunction "P4.6/TB6_42") (pintype "passive"))
      (node (ref "U9") (pin "17") (pinfunction "SRADD2_17") (pintype "passive"))
    )
    (net (code "55") (name "/STADD0") (class "Default")
      (node (ref "U7") (pin "37") (pinfunction "P4.1/TB1_37") (pintype "passive"))
      (node (ref "U9") (pin "22") (pinfunction "STADD0_22") (pintype "passive"))
    )
    (net (code "56") (name "/STADD1") (class "Default")
      (node (ref "U7") (pin "38") (pinfunction "P4.2/TB2_38") (pintype "passive"))
      (node (ref "U9") (pin "21") (pinfunction "STADD1_21") (pintype "passive"))
    )
    (net (code "57") (name "/STADD2") (class "Default")
      (node (ref "U7") (pin "39") (pinfunction "P4.3/TB3_39") (pintype "passive"))
      (node (ref "U9") (pin "20") (pinfunction "STADD2_20") (pintype "passive"))
    )
    (net (code "58") (name "/Socket0_CS") (class "Default")
      (node (ref "JP3") (pin "3") (pinfunction "3_3") (pintype "passive"))
      (node (ref "U7") (pin "27") (pinfunction "P2.7/TA0_27") (pintype "passive"))
    )
    (net (code "59") (name "/Socket1_CS") (class "Default")
      (node (ref "JP5") (pin "3") (pinfunction "3_3") (pintype "passive"))
      (node (ref "U7") (pin "26") (pinfunction "P2.6/ADC12CLK_26") (pintype "passive"))
    )
    (net (code "60") (name "/TCK") (class "Default")
      (node (ref "P2") (pin "7") (pinfunction "7_7") (pintype "passive"))
      (node (ref "U7") (pin "57") (pinfunction "TCK_57") (pintype "passive"))
    )
    (net (code "61") (name "/TDI") (class "Default")
      (node (ref "P2") (pin "3") (pinfunction "3_3") (pintype "passive"))
      (node (ref "U7") (pin "55") (pinfunction "TDI_55") (pintype "passive"))
    )
    (net (code "62") (name "/TDO") (class "Default")
      (node (ref "P2") (pin "1") (pinfunction "1_1") (pintype "passive"))
      (node (ref "U7") (pin "54") (pinfunction "TDO/TDI_54") (pintype "passive"))
    )
    (net (code "63") (name "/TMS") (class "Default")
      (node (ref "P2") (pin "5") (pinfunction "5_5") (pintype "passive"))
      (node (ref "U7") (pin "56") (pinfunction "TMS_56") (pintype "passive"))
    )
    (net (code "64") (name "/TXD0") (class "Default")
      (node (ref "JP3") (pin "1") (pinfunction "1_1") (pintype "passive"))
      (node (ref "JP5") (pin "1") (pinfunction "1_1") (pintype "passive"))
      (node (ref "U7") (pin "32") (pinfunction "P3.4/UTXD0_32") (pintype "passive"))
    )
    (net (code "65") (name "/TXD1") (class "Default")
      (node (ref "U7") (pin "34") (pinfunction "P3.6/UTXD1_34") (pintype "passive"))
      (node (ref "U9") (pin "14") (pinfunction "RXD0_14") (pintype "passive"))
    )
    (net (code "66") (name "/VCC_GPS_3.3V") (class "Default")
      (node (ref "J4") (pin "1") (pinfunction "1_1") (pintype "passive"))
      (node (ref "Q3") (pin "3") (pinfunction "S_3") (pintype "input"))
    )
    (net (code "67") (name "/VCC_Sensor_3.3V") (class "Default")
      (node (ref "JP1") (pin "22") (pinfunction "22_22") (pintype "passive"))
      (node (ref "Q11") (pin "3") (pinfunction "S_3") (pintype "input"))
    )
    (net (code "68") (name "/VCC_Sensor_5V") (class "Default")
      (node (ref "JP1") (pin "20") (pinfunction "20_20") (pintype "passive"))
      (node (ref "Q9") (pin "3") (pinfunction "S_3") (pintype "input"))
    )
    (net (code "69") (name "/VCC_Socket_3.3V") (class "Default")
      (node (ref "JP2") (pin "5") (pinfunction "5_5") (pintype "passive"))
      (node (ref "JP4") (pin "5") (pinfunction "5_5") (pintype "passive"))
      (node (ref "Q4") (pin "3") (pinfunction "S_3") (pintype "input"))
    )
    (net (code "70") (name "/VCC_Socket_5V") (class "Default")
      (node (ref "JP2") (pin "3") (pinfunction "3_3") (pintype "passive"))
      (node (ref "JP4") (pin "3") (pinfunction "3_3") (pintype "passive"))
      (node (ref "Q12") (pin "3") (pinfunction "S_3") (pintype "input"))
    )
    (net (code "71") (name "/VREF+") (class "Default")
      (node (ref "C20") (pin "2") (pinfunction "2_2") (pintype "passive"))
      (node (ref "U7") (pin "7") (pinfunction "VREF+_7") (pintype "passive"))
    )
    (net (code "72") (name "/VREF-") (class "Default")
      (node (ref "C25") (pin "1") (pinfunction "1_1") (pintype "passive"))
      (node (ref "U7") (pin "11") (pinfunction "VREF-/VeREF-_11") (pintype "passive"))
    )
    (net (code "73") (name "/VeREF+") (class "Default")
      (node (ref "C24") (pin "1") (pinfunction "1_1") (pintype "passive"))
      (node (ref "U7") (pin "10") (pinfunction "VeREF+_10") (pintype "passive"))
    )
    (net (code "74") (name "BAT") (class "Default")
      (node (ref "C2") (pin "2") (pinfunction "2_2") (pintype "passive"))
      (node (ref "J1") (pin "2") (pinfunction "2_2") (pintype "passive"))
      (node (ref "S1") (pin "1") (pinfunction "1_1") (pintype "passive"))
      (node (ref "U2") (pin "3") (pinfunction "BAT_3") (pintype "passive"))
    )
    (net (code "75") (name "GND") (class "Default")
      (node (ref "C1") (pin "2") (pinfunction "2_2") (pintype "passive"))
      (node (ref "C10") (pin "2") (pinfunction "2_2") (pintype "passive"))
      (node (ref "C11") (pin "1") (pinfunction "1_1") (pintype "passive"))
      (node (ref "C12") (pin "2") (pinfunction "2_2") (pintype "passive"))
      (node (ref "C13") (pin "1") (pinfunction "1_1") (pintype "passive"))
      (node (ref "C132") (pin "2") (pinfunction "2_2") (pintype "passive"))
      (node (ref "C14") (pin "2") (pinfunction "2_2") (pintype "passive"))
      (node (ref "C142") (pin "2") (pinfunction "2_2") (pintype "passive"))
      (node (ref "C15") (pin "2") (pinfunction "2_2") (pintype "passive"))
      (node (ref "C16") (pin "2") (pinfunction "2_2") (pintype "passive"))
      (node (ref "C17") (pin "2") (pinfunction "2_2") (pintype "passive"))
      (node (ref "C18") (pin "2") (pinfunction "2_2") (pintype "passive"))
      (node (ref "C19") (pin "1") (pinfunction "1_1") (pintype "passive"))
      (node (ref "C2") (pin "1") (pinfunction "1_1") (pintype "passive"))
      (node (ref "C20") (pin "1") (pinfunction "1_1") (pintype "passive"))
      (node (ref "C21") (pin "1") (pinfunction "1_1") (pintype "passive"))
      (node (ref "C22") (pin "2") (pinfunction "2_2") (pintype "passive"))
      (node (ref "C23") (pin "2") (pinfunction "2_2") (pintype "passive"))
      (node (ref "C24") (pin "2") (pinfunction "2_2") (pintype "passive"))
      (node (ref "C25") (pin "2") (pinfunction "2_2") (pintype "passive"))
      (node (ref "C26") (pin "1") (pinfunction "1_1") (pintype "passive"))
      (node (ref "C27") (pin "1") (pinfunction "1_1") (pintype "passive"))
      (node (ref "C28") (pin "2") (pinfunction "2_2") (pintype "passive"))
      (node (ref "C29") (pin "2") (pinfunction "2_2") (pintype "passive"))
      (node (ref "C3") (pin "2") (pinfunction "2_2") (pintype "passive"))
      (node (ref "C30") (pin "1") (pinfunction "1_1") (pintype "passive"))
      (node (ref "C31") (pin "1") (pinfunction "1_1") (pintype "passive"))
      (node (ref "C4") (pin "1") (pinfunction "1_1") (pintype "passive"))
      (node (ref "C5") (pin "1") (pinfunction "1_1") (pintype "passive"))
      (node (ref "C6") (pin "1") (pinfunction "1_1") (pintype "passive"))
      (node (ref "C7") (pin "2") (pinfunction "2_2") (pintype "passive"))
      (node (ref "C8") (pin "2") (pinfunction "2_2") (pintype "passive"))
      (node (ref "C9") (pin "2") (pinfunction "2_2") (pintype "passive"))
      (node (ref "D4") (pin "K") (pinfunction "2_K") (pintype "passive"))
      (node (ref "J1") (pin "1") (pinfunction "1_1") (pintype "passive"))
      (node (ref "J2") (pin "1") (pinfunction "1_1") (pintype "passive"))
      (node (ref "J4") (pin "2") (pinfunction "2_2") (pintype "passive"))
      (node (ref "J4") (pin "5") (pinfunction "5_5") (pintype "passive"))
      (node (ref "J5") (pin "2") (pinfunction "2_2") (pintype "passive"))
      (node (ref "JP1") (pin "23") (pinfunction "23_23") (pintype "passive"))
      (node (ref "JP2") (pin "4") (pinfunction "4_4") (pintype "passive"))
      (node (ref "JP2") (pin "6") (pinfunction "6_6") (pintype "passive"))
      (node (ref "JP3") (pin "8") (pinfunction "8_8") (pintype "passive"))
      (node (ref "JP4") (pin "4") (pinfunction "4_4") (pintype "passive"))
      (node (ref "JP4") (pin "6") (pinfunction "6_6") (pintype "passive"))
      (node (ref "JP5") (pin "8") (pinfunction "8_8") (pintype "passive"))
      (node (ref "JP6") (pin "2") (pinfunction "2_2") (pintype "passive"))
      (node (ref "JP6") (pin "5") (pinfunction "5_5") (pintype "passive"))
      (node (ref "JP6") (pin "8") (pinfunction "8_8") (pintype "passive"))
      (node (ref "K1") (pin "1") (pinfunction "1_1") (pintype "passive"))
      (node (ref "P1") (pin "4") (pinfunction "GND_4") (pintype "power_in"))
      (node (ref "P2") (pin "9") (pinfunction "9_9") (pintype "passive"))
      (node (ref "Q1") (pin "2") (pinfunction "E_2") (pintype "passive"))
      (node (ref "Q2") (pin "2") (pinfunction "E_2") (pintype "passive"))
      (node (ref "Q5") (pin "2") (pinfunction "E_2") (pintype "passive"))
      (node (ref "Q6") (pin "2") (pinfunction "E_2") (pintype "passive"))
      (node (ref "Q7") (pin "2") (pinfunction "E_2") (pintype "passive"))
      (node (ref "Q8") (pin "2") (pinfunction "E_2") (pintype "passive"))
      (node (ref "R23") (pin "1") (pinfunction "1_1") (pintype "passive"))
      (node (ref "R24") (pin "1") (pinfunction "1_1") (pintype "passive"))
      (node (ref "R29") (pin "2") (pinfunction "2_2") (pintype "passive"))
      (node (ref "R7") (pin "1") (pinfunction "1_1") (pintype "passive"))
      (node (ref "R9") (pin "2") (pinfunction "2_2") (pintype "passive"))
      (node (ref "SD1") (pin "10") (pinfunction "COM_10") (pintype "passive"))
      (node (ref "SD1") (pin "11") (pinfunction "COM_11") (pintype "passive"))
      (node (ref "SD1") (pin "12") (pinfunction "COM_12") (pintype "passive"))
      (node (ref "SD1") (pin "6") (pinfunction "VSS_6") (pintype "passive"))
      (node (ref "U1") (pin "11") (pinfunction "EPAD_11") (pintype "passive"))
      (node (ref "U1") (pin "3") (pinfunction "PGND_3") (pintype "passive"))
      (node (ref "U1") (pin "9") (pinfunction "GND_9") (pintype "passive"))
      (node (ref "U2") (pin "2") (pinfunction "GND_2") (pintype "passive"))
      (node (ref "U3") (pin "2") (pinfunction "GND_2") (pintype "passive"))
      (node (ref "U4") (pin "2") (pinfunction "GND_2") (pintype "passive"))
      (node (ref "U4") (pin "4") (pinfunction "GND_4") (pintype "passive"))
      (node (ref "U4") (pin "5") (pinfunction "GND_5") (pintype "passive"))
      (node (ref "U5") (pin "10") (pinfunction "NC_10") (pintype "passive"))
      (node (ref "U5") (pin "11") (pinfunction "NC_11") (pintype "passive"))
      (node (ref "U5") (pin "12") (pinfunction "NC_12") (pintype "passive"))
      (node (ref "U5") (pin "5") (pinfunction "NC_5") (pintype "passive"))
      (node (ref "U5") (pin "6") (pinfunction "NC_6") (pintype "passive"))
      (node (ref "U5") (pin "7") (pinfunction "NC_7") (pintype "passive"))
      (node (ref "U5") (pin "8") (pinfunction "NC_8") (pintype "passive"))
      (node (ref "U5") (pin "9") (pinfunction "NC_9") (pintype "passive"))
      (node (ref "U52") (pin "1") (pinfunction "Gnd_1") (pintype "passive"))
      (node (ref "U6") (pin "1") (pinfunction "A0_1") (pintype "passive"))
      (node (ref "U6") (pin "2") (pinfunction "A1_2") (pintype "passive"))
      (node (ref "U6") (pin "3") (pinfunction "A2_3") (pintype "passive"))
      (node (ref "U6") (pin "4") (pinfunction "GND_4") (pintype "passive"))
      (node (ref "U6") (pin "7") (pinfunction "WP_7") (pintype "passive"))
      (node (ref "U7") (pin "62") (pinfunction "AVss_62") (pintype "passive"))
      (node (ref "U7") (pin "63") (pinfunction "DVss_63") (pintype "passive"))
      (node (ref "U8") (pin "18") (pinfunction "GND_18") (pintype "passive"))
      (node (ref "U8") (pin "21") (pinfunction "GND_21") (pintype "passive"))
      (node (ref "U8") (pin "22") (pinfunction "GP0_22") (pintype "passive"))
      (node (ref "U8") (pin "23") (pinfunction "GP1_23") (pintype "passive"))
      (node (ref "U8") (pin "25") (pinfunction "GND_A_25") (pintype "passive"))
      (node (ref "U8") (pin "26") (pinfunction "PLL_TEST_26") (pintype "passive"))
      (node (ref "U8") (pin "7") (pinfunction "GND_7") (pintype "passive"))
      (node (ref "U9") (pin "12") (pinfunction "GND_12") (pintype "passive"))
    )
    (net (code "76") (name "Net-(C30-Pad2)") (class "Default")
      (node (ref "C30") (pin "2") (pinfunction "2_2") (pintype "passive"))
      (node (ref "R35") (pin "2") (pinfunction "2_2") (pintype "passive"))
      (node (ref "U8") (pin "17") (pinfunction "VDD_17") (pintype "passive"))
    )
    (net (code "77") (name "Net-(D1-2)") (class "Default")
      (node (ref "D1") (pin "K") (pinfunction "2_K") (pintype "passive"))
      (node (ref "U2") (pin "1") (pinfunction "~{CHRG}_1") (pintype "passive"))
    )
    (net (code "78") (name "Net-(D2-2)") (class "Default")
      (node (ref "D2") (pin "K") (pinfunction "2_K") (pintype "passive"))
      (node (ref "U2") (pin "5") (pinfunction "~{STDBY}_5") (pintype "passive"))
    )
    (net (code "79") (name "Net-(D3-A)") (class "Default")
      (node (ref "D3") (pin "1") (pinfunction "A_1") (pintype "passive"))
      (node (ref "L2") (pin "2") (pinfunction "2_2") (pintype "passive"))
      (node (ref "U3") (pin "1") (pinfunction "LX_1") (pintype "passive"))
    )
    (net (code "80") (name "Net-(D4-1)") (class "Default")
      (node (ref "D4") (pin "A") (pinfunction "1_A") (pintype "passive"))
      (node (ref "R25") (pin "1") (pinfunction "1_1") (pintype "passive"))
    )
    (net (code "81") (name "Net-(Q1-B)") (class "Default")
      (node (ref "Q1") (pin "1") (pinfunction "B_1") (pintype "passive"))
      (node (ref "R5") (pin "2") (pinfunction "2_2") (pintype "passive"))
    )
    (net (code "82") (name "Net-(Q1-C)") (class "Default")
      (node (ref "Q1") (pin "3") (pinfunction "C_3") (pintype "passive"))
      (node (ref "R1") (pin "2") (pinfunction "2_2") (pintype "passive"))
      (node (ref "R3") (pin "2") (pinfunction "2_2") (pintype "passive"))
    )
    (net (code "83") (name "Net-(Q2-B)") (class "Default")
      (node (ref "Q2") (pin "1") (pinfunction "B_1") (pintype "passive"))
      (node (ref "R6") (pin "2") (pinfunction "2_2") (pintype "passive"))
    )
    (net (code "84") (name "Net-(Q2-C)") (class "Default")
      (node (ref "Q2") (pin "3") (pinfunction "C_3") (pintype "passive"))
      (node (ref "R2") (pin "2") (pinfunction "2_2") (pintype "passive"))
      (node (ref "R4") (pin "2") (pinfunction "2_2") (pintype "passive"))
    )
    (net (code "85") (name "Net-(Q3-G)") (class "Default")
      (node (ref "Q3") (pin "1") (pinfunction "G_1") (pintype "input"))
      (node (ref "R1") (pin "1") (pinfunction "1_1") (pintype "passive"))
    )
    (net (code "86") (name "Net-(Q4-G)") (class "Default")
      (node (ref "Q4") (pin "1") (pinfunction "G_1") (pintype "input"))
      (node (ref "R2") (pin "1") (pinfunction "1_1") (pintype "passive"))
    )
    (net (code "87") (name "Net-(Q5-B)") (class "Default")
      (node (ref "Q5") (pin "1") (pinfunction "B_1") (pintype "passive"))
      (node (ref "R19") (pin "2") (pinfunction "2_2") (pintype "passive"))
    )
    (net (code "88") (name "Net-(Q5-C)") (class "Default")
      (node (ref "Q5") (pin "3") (pinfunction "C_3") (pintype "passive"))
      (node (ref "R10") (pin "2") (pinfunction "2_2") (pintype "passive"))
      (node (ref "R15") (pin "2") (pinfunction "2_2") (pintype "passive"))
    )
    (net (code "89") (name "Net-(Q6-B)") (class "Default")
      (node (ref "Q6") (pin "1") (pinfunction "B_1") (pintype "passive"))
      (node (ref "R20") (pin "2") (pinfunction "2_2") (pintype "passive"))
    )
    (net (code "90") (name "Net-(Q6-C)") (class "Default")
      (node (ref "Q6") (pin "3") (pinfunction "C_3") (pintype "passive"))
      (node (ref "R11") (pin "2") (pinfunction "2_2") (pintype "passive"))
      (node (ref "R16") (pin "2") (pinfunction "2_2") (pintype "passive"))
    )
    (net (code "91") (name "Net-(Q7-B)") (class "Default")
      (node (ref "Q7") (pin "1") (pinfunction "B_1") (pintype "passive"))
      (node (ref "R21") (pin "2") (pinfunction "2_2") (pintype "passive"))
    )
    (net (code "92") (name "Net-(Q7-C)") (class "Default")
      (node (ref "Q7") (pin "3") (pinfunction "C_3") (pintype "passive"))
      (node (ref "R12") (pin "2") (pinfunction "2_2") (pintype "passive"))
      (node (ref "R17") (pin "2") (pinfunction "2_2") (pintype "passive"))
    )
    (net (code "93") (name "Net-(Q8-B)") (class "Default")
      (node (ref "Q8") (pin "1") (pinfunction "B_1") (pintype "passive"))
      (node (ref "R22") (pin "2") (pinfunction "2_2") (pintype "passive"))
    )
    (net (code "94") (name "Net-(Q8-C)") (class "Default")
      (node (ref "Q8") (pin "3") (pinfunction "C_3") (pintype "passive"))
      (node (ref "R13") (pin "2") (pinfunction "2_2") (pintype "passive"))
      (node (ref "R18") (pin "2") (pinfunction "2_2") (pintype "passive"))
    )
    (net (code "95") (name "Net-(Q9-G)") (class "Default")
      (node (ref "Q9") (pin "1") (pinfunction "G_1") (pintype "input"))
      (node (ref "R10") (pin "1") (pinfunction "1_1") (pintype "passive"))
    )
    (net (code "96") (name "Net-(Q10-G)") (class "Default")
      (node (ref "Q10") (pin "1") (pinfunction "G_1") (pintype "input"))
      (node (ref "R11") (pin "1") (pinfunction "1_1") (pintype "passive"))
    )
    (net (code "97") (name "Net-(Q11-G)") (class "Default")
      (node (ref "Q11") (pin "1") (pinfunction "G_1") (pintype "input"))
      (node (ref "R12") (pin "1") (pinfunction "1_1") (pintype "passive"))
    )
    (net (code "98") (name "Net-(Q12-G)") (class "Default")
      (node (ref "Q12") (pin "1") (pinfunction "G_1") (pintype "input"))
      (node (ref "R13") (pin "1") (pinfunction "1_1") (pintype "passive"))
    )
    (net (code "99") (name "Net-(SD1-DAT1)") (class "Default")
      (node (ref "R42") (pin "2") (pinfunction "2_2") (pintype "passive"))
      (node (ref "SD1") (pin "8") (pinfunction "DAT1_8") (pintype "passive"))
    )
    (net (code "100") (name "Net-(SD1-DAT2)") (class "Default")
      (node (ref "R41") (pin "2") (pinfunction "2_2") (pintype "passive"))
      (node (ref "SD1") (pin "1") (pinfunction "DAT2_1") (pintype "passive"))
    )
    (net (code "101") (name "Net-(U1-L1)") (class "Default")
      (node (ref "L1") (pin "2") (pinfunction "2_2") (pintype "passive"))
      (node (ref "U1") (pin "4") (pinfunction "L1_4") (pintype "passive"))
    )
    (net (code "102") (name "Net-(U1-L2)") (class "Default")
      (node (ref "L1") (pin "1") (pinfunction "1_1") (pintype "passive"))
      (node (ref "U1") (pin "2") (pinfunction "L2_2") (pintype "passive"))
    )
    (net (code "103") (name "Net-(U2-PROG)") (class "Default")
      (node (ref "R7") (pin "2") (pinfunction "2_2") (pintype "passive"))
      (node (ref "U2") (pin "6") (pinfunction "PROG_6") (pintype "passive"))
    )
    (net (code "104") (name "Net-(U3-FB)") (class "Default")
      (node (ref "R14") (pin "1") (pinfunction "1_1") (pintype "passive"))
      (node (ref "R24") (pin "2") (pinfunction "2_2") (pintype "passive"))
      (node (ref "U3") (pin "3") (pinfunction "FB_3") (pintype "passive"))
    )
    (net (code "105") (name "Net-(U3-OC)") (class "Default")
      (node (ref "R23") (pin "2") (pinfunction "2_2") (pintype "passive"))
      (node (ref "U3") (pin "6") (pinfunction "OC_6") (pintype "passive"))
    )
    (net (code "106") (name "Net-(U4-SDO)") (class "Default")
      (node (ref "R29") (pin "1") (pinfunction "1_1") (pintype "passive"))
      (node (ref "U4") (pin "12") (pinfunction "SDO_12") (pintype "passive"))
    )
    (net (code "107") (name "Net-(U4-Vs)") (class "Default")
      (node (ref "R27") (pin "2") (pinfunction "2_2") (pintype "passive"))
      (node (ref "U4") (pin "6") (pinfunction "Vs_6") (pintype "passive"))
    )
    (net (code "108") (name "Net-(U4-~{C}S)") (class "Default")
      (node (ref "R30") (pin "2") (pinfunction "2_2") (pintype "passive"))
      (node (ref "U4") (pin "7") (pinfunction "~{C}S_7") (pintype "passive"))
    )
    (net (code "109") (name "Net-(U5-32KHz)") (class "Default")
      (node (ref "R28") (pin "1") (pinfunction "1_1") (pintype "passive"))
      (node (ref "U5") (pin "1") (pinfunction "32KHz_1") (pintype "passive"))
    )
    (net (code "110") (name "Net-(U7-XIN)") (class "Default")
      (node (ref "C19") (pin "2") (pinfunction "2_2") (pintype "passive"))
      (node (ref "U7") (pin "8") (pinfunction "XIN_8") (pintype "passive"))
      (node (ref "XT2") (pin "2") (pinfunction "2_2") (pintype "passive"))
    )
    (net (code "111") (name "Net-(U7-XOUT{slash}TCLK)") (class "Default")
      (node (ref "C21") (pin "2") (pinfunction "2_2") (pintype "passive"))
      (node (ref "U7") (pin "9") (pinfunction "XOUT/TCLK_9") (pintype "passive"))
      (node (ref "XT2") (pin "1") (pinfunction "1_1") (pintype "passive"))
    )
    (net (code "112") (name "Net-(U7-XT2IN)") (class "Default")
      (node (ref "C13") (pin "2") (pinfunction "2_2") (pintype "passive"))
      (node (ref "U7") (pin "53") (pinfunction "XT2IN_53") (pintype "passive"))
      (node (ref "XT1") (pin "2") (pinfunction "2_2") (pintype "passive"))
    )
    (net (code "113") (name "Net-(U7-XT2OUT)") (class "Default")
      (node (ref "C11") (pin "2") (pinfunction "2_2") (pintype "passive"))
      (node (ref "U7") (pin "52") (pinfunction "XT2OUT_52") (pintype "passive"))
      (node (ref "XT1") (pin "1") (pinfunction "1_1") (pintype "passive"))
    )
    (net (code "114") (name "Net-(U8-DM)") (class "Default")
      (node (ref "R38") (pin "2") (pinfunction "2_2") (pintype "passive"))
      (node (ref "U8") (pin "16") (pinfunction "DM_16") (pintype "passive"))
    )
    (net (code "115") (name "Net-(U8-DP)") (class "Default")
      (node (ref "R40") (pin "2") (pinfunction "2_2") (pintype "passive"))
      (node (ref "U8") (pin "15") (pinfunction "DP_15") (pintype "passive"))
    )
    (net (code "116") (name "Net-(U8-EECLK)") (class "Default")
      (node (ref "R37") (pin "1") (pinfunction "1_1") (pintype "passive"))
      (node (ref "U8") (pin "13") (pinfunction "EECLK_13") (pintype "passive"))
    )
    (net (code "117") (name "Net-(U8-EE_DATA)") (class "Default")
      (node (ref "R39") (pin "1") (pinfunction "1_1") (pintype "passive"))
      (node (ref "U8") (pin "14") (pinfunction "EE_DATA_14") (pintype "passive"))
    )
    (net (code "118") (name "Net-(U8-OSC1)") (class "Default")
      (node (ref "C28") (pin "1") (pinfunction "1_1") (pintype "passive"))
      (node (ref "U8") (pin "27") (pinfunction "OSC1_27") (pintype "passive"))
      (node (ref "XT4") (pin "1") (pinfunction "1_1") (pintype "passive"))
    )
    (net (code "119") (name "Net-(U8-OSC2)") (class "Default")
      (node (ref "C22") (pin "1") (pinfunction "1_1") (pintype "passive"))
      (node (ref "U8") (pin "28") (pinfunction "OSC2_28") (pintype "passive"))
      (node (ref "XT4") (pin "2") (pinfunction "2_2") (pintype "passive"))
    )
    (net (code "120") (name "Net-(U8-RXD)") (class "Default")
      (node (ref "R34") (pin "1") (pinfunction "1_1") (pintype "passive"))
      (node (ref "U8") (pin "5") (pinfunction "RXD_5") (pintype "passive"))
    )
    (net (code "121") (name "Net-(U8-TXD)") (class "Default")
      (node (ref "R33") (pin "1") (pinfunction "1_1") (pintype "passive"))
      (node (ref "U8") (pin "1") (pinfunction "TXD_1") (pintype "passive"))
    )
    (net (code "122") (name "Net-(U9-OSCI)") (class "Default")
      (node (ref "C23") (pin "1") (pinfunction "1_1") (pintype "passive"))
      (node (ref "U9") (pin "1") (pinfunction "OSCI_1") (pintype "passive"))
      (node (ref "XT3") (pin "2") (pinfunction "2_2") (pintype "passive"))
    )
    (net (code "123") (name "Net-(U9-OSCO)") (class "Default")
      (node (ref "C26") (pin "2") (pinfunction "2_2") (pintype "passive"))
      (node (ref "U9") (pin "2") (pinfunction "OSCO_2") (pintype "passive"))
      (node (ref "XT3") (pin "1") (pinfunction "1_1") (pintype "passive"))
    )
    (net (code "124") (name "VBUS") (class "Default")
      (node (ref "C10") (pin "1") (pinfunction "1_1") (pintype "passive"))
      (node (ref "C4") (pin "2") (pinfunction "2_2") (pintype "passive"))
      (node (ref "C5") (pin "2") (pinfunction "2_2") (pintype "passive"))
      (node (ref "C9") (pin "1") (pinfunction "1_1") (pintype "passive"))
      (node (ref "J5") (pin "5") (pinfunction "5_5") (pintype "passive"))
      (node (ref "JP1") (pin "21") (pinfunction "21_21") (pintype "passive"))
      (node (ref "JP3") (pin "7") (pinfunction "7_7") (pintype "passive"))
      (node (ref "JP5") (pin "7") (pinfunction "7_7") (pintype "passive"))
      (node (ref "JP6") (pin "1") (pinfunction "1_1") (pintype "passive"))
      (node (ref "L2") (pin "1") (pinfunction "1_1") (pintype "passive"))
      (node (ref "R8") (pin "2") (pinfunction "2_2") (pintype "passive"))
      (node (ref "S1") (pin "2") (pinfunction "2_2") (pintype "passive"))
      (node (ref "U1") (pin "5") (pinfunction "VIN_5") (pintype "passive"))
      (node (ref "U1") (pin "6") (pinfunction "EN_6") (pintype "passive"))
      (node (ref "U1") (pin "7") (pinfunction "PS/SYNC_7") (pintype "passive"))
      (node (ref "U1") (pin "8") (pinfunction "VINA_8") (pintype "passive"))
      (node (ref "U3") (pin "4") (pinfunction "EN_4") (pintype "passive"))
      (node (ref "U3") (pin "5") (pinfunction "VCC_5") (pintype "passive"))
    )
    (net (code "125") (name "VCC_Base_3.3V") (class "Default")
      (node (ref "C1") (pin "1") (pinfunction "1_1") (pintype "passive"))
      (node (ref "C12") (pin "1") (pinfunction "1_1") (pintype "passive"))
      (node (ref "C14") (pin "1") (pinfunction "1_1") (pintype "passive"))
      (node (ref "C142") (pin "1") (pinfunction "1_1") (pintype "passive"))
      (node (ref "C16") (pin "1") (pinfunction "1_1") (pintype "passive"))
      (node (ref "C17") (pin "1") (pinfunction "1_1") (pintype "passive"))
      (node (ref "C18") (pin "1") (pinfunction "1_1") (pintype "passive"))
      (node (ref "C27") (pin "2") (pinfunction "2_2") (pintype "passive"))
      (node (ref "C29") (pin "1") (pinfunction "1_1") (pintype "passive"))
      (node (ref "D5") (pin "2") (pinfunction "K_2") (pintype "passive"))
      (node (ref "Q10") (pin "2") (pinfunction "D_2") (pintype "input"))
      (node (ref "Q11") (pin "2") (pinfunction "D_2") (pintype "input"))
      (node (ref "Q3") (pin "2") (pinfunction "D_2") (pintype "input"))
      (node (ref "Q4") (pin "2") (pinfunction "D_2") (pintype "input"))
      (node (ref "R16") (pin "1") (pinfunction "1_1") (pintype "passive"))
      (node (ref "R17") (pin "1") (pinfunction "1_1") (pintype "passive"))
      (node (ref "R26") (pin "2") (pinfunction "2_2") (pintype "passive"))
      (node (ref "R27") (pin "1") (pinfunction "1_1") (pintype "passive"))
      (node (ref "R28") (pin "2") (pinfunction "2_2") (pintype "passive"))
      (node (ref "R3") (pin "1") (pinfunction "1_1") (pintype "passive"))
      (node (ref "R30") (pin "1") (pinfunction "1_1") (pintype "passive"))
      (node (ref "R31") (pin "2") (pinfunction "2_2") (pintype "passive"))
      (node (ref "R32") (pin "2") (pinfunction "2_2") (pintype "passive"))
      (node (ref "R36") (pin "1") (pinfunction "1_1") (pintype "passive"))
      (node (ref "R37") (pin "2") (pinfunction "2_2") (pintype "passive"))
      (node (ref "R39") (pin "2") (pinfunction "2_2") (pintype "passive"))
      (node (ref "R4") (pin "1") (pinfunction "1_1") (pintype "passive"))
      (node (ref "U1") (pin "1") (pinfunction "Vout_1") (pintype "passive"))
      (node (ref "U1") (pin "10") (pinfunction "FB_10") (pintype "passive"))
      (node (ref "U4") (pin "1") (pinfunction "Vdd_1") (pintype "passive"))
      (node (ref "U5") (pin "2") (pinfunction "VCC_2") (pintype "passive"))
      (node (ref "U52") (pin "2") (pinfunction "Vout_2") (pintype "passive"))
      (node (ref "U52") (pin "4") (pinfunction "4_4") (pintype "passive"))
      (node (ref "U6") (pin "8") (pinfunction "VCC_8") (pintype "passive"))
      (node (ref "U7") (pin "1") (pinfunction "DVCC_1") (pintype "passive"))
      (node (ref "U7") (pin "64") (pinfunction "AVcc_64") (pintype "passive"))
      (node (ref "U8") (pin "4") (pinfunction "VDD_4") (pintype "passive"))
      (node (ref "U9") (pin "24") (pinfunction "VDD_24") (pintype "passive"))
    )
    (net (code "126") (name "VCC_Base_5V") (class "Default")
      (node (ref "C132") (pin "1") (pinfunction "1_1") (pintype "passive"))
      (node (ref "C7") (pin "1") (pinfunction "1_1") (pintype "passive"))
      (node (ref "C8") (pin "1") (pinfunction "1_1") (pintype "passive"))
      (node (ref "D3") (pin "2") (pinfunction "K_2") (pintype "passive"))
      (node (ref "J5") (pin "1") (pinfunction "1_1") (pintype "passive"))
      (node (ref "JP1") (pin "24") (pinfunction "24_24") (pintype "passive"))
      (node (ref "JP16") (pin "2") (pinfunction "2_2") (pintype "passive"))
      (node (ref "Q12") (pin "2") (pinfunction "D_2") (pintype "input"))
      (node (ref "Q9") (pin "2") (pinfunction "D_2") (pintype "input"))
      (node (ref "R14") (pin "2") (pinfunction "2_2") (pintype "passive"))
      (node (ref "R15") (pin "1") (pinfunction "1_1") (pintype "passive"))
      (node (ref "R18") (pin "1") (pinfunction "1_1") (pintype "passive"))
      (node (ref "U52") (pin "3") (pinfunction "Vin_3") (pintype "passive"))
      (node (ref "U8") (pin "19") (pinfunction "NC_19") (pintype "passive"))
      (node (ref "U8") (pin "20") (pinfunction "VDD_20") (pintype "passive"))
    )
    (net (code "127") (name "VCC_SD_3.3V") (class "Default")
      (node (ref "C31") (pin "2") (pinfunction "2_2") (pintype "passive"))
      (node (ref "Q10") (pin "3") (pinfunction "S_3") (pintype "input"))
      (node (ref "R41") (pin "1") (pinfunction "1_1") (pintype "passive"))
      (node (ref "R42") (pin "1") (pinfunction "1_1") (pintype "passive"))
      (node (ref "SD1") (pin "4") (pinfunction "VDD_4") (pintype "passive"))
    )
    (net (code "128") (name "VIN") (class "Default")
      (node (ref "C6") (pin "2") (pinfunction "2_2") (pintype "passive"))
      (node (ref "D1") (pin "A") (pinfunction "1_A") (pintype "passive"))
      (node (ref "D2") (pin "A") (pinfunction "1_A") (pintype "passive"))
      (node (ref "J2") (pin "2") (pinfunction "2_2") (pintype "passive"))
      (node (ref "JP16") (pin "1") (pinfunction "1_1") (pintype "passive"))
      (node (ref "P1") (pin "1") (pinfunction "VCC_1") (pintype "power_in"))
      (node (ref "U2") (pin "4") (pinfunction "VCC_4") (pintype "passive"))
    )
    (net (code "129") (name "unconnected-(HO1-A-Pad1)") (class "Default")
      (node (ref "HO1") (pin "1") (pinfunction "A_1") (pintype "passive"))
    )
    (net (code "130") (name "unconnected-(HO2-A-Pad1)") (class "Default")
      (node (ref "HO2") (pin "1") (pinfunction "A_1") (pintype "passive"))
    )
    (net (code "131") (name "unconnected-(HO3-A-Pad1)") (class "Default")
      (node (ref "HO3") (pin "1") (pinfunction "A_1") (pintype "passive"))
    )
    (net (code "132") (name "unconnected-(HO4-A-Pad1)") (class "Default")
      (node (ref "HO4") (pin "1") (pinfunction "A_1") (pintype "passive"))
    )
    (net (code "133") (name "unconnected-(P2-Pad2)") (class "Default")
      (node (ref "P2") (pin "2") (pinfunction "2_2") (pintype "passive"))
    )
    (net (code "134") (name "unconnected-(P2-Pad4)") (class "Default")
      (node (ref "P2") (pin "4") (pinfunction "4_4") (pintype "passive"))
    )
    (net (code "135") (name "unconnected-(P2-Pad6)") (class "Default")
      (node (ref "P2") (pin "6") (pinfunction "6_6") (pintype "passive"))
    )
    (net (code "136") (name "unconnected-(P2-Pad8)") (class "Default")
      (node (ref "P2") (pin "8") (pinfunction "8_8") (pintype "passive"))
    )
    (net (code "137") (name "unconnected-(P2-Pad10)") (class "Default")
      (node (ref "P2") (pin "10") (pinfunction "10_10") (pintype "passive"))
    )
    (net (code "138") (name "unconnected-(P2-Pad12)") (class "Default")
      (node (ref "P2") (pin "12") (pinfunction "12_12") (pintype "passive"))
    )
    (net (code "139") (name "unconnected-(P2-Pad13)") (class "Default")
      (node (ref "P2") (pin "13") (pinfunction "13_13") (pintype "passive"))
    )
    (net (code "140") (name "unconnected-(P2-Pad14)") (class "Default")
      (node (ref "P2") (pin "14") (pinfunction "14_14") (pintype "passive"))
    )
    (net (code "141") (name "unconnected-(S1-Pad3)") (class "Default")
      (node (ref "S1") (pin "3") (pinfunction "3_3") (pintype "passive"))
    )
    (net (code "142") (name "unconnected-(SD1-COM-Pad9)") (class "Default")
      (node (ref "SD1") (pin "9") (pinfunction "COM_9") (pintype "passive+no_connect"))
    )
    (net (code "143") (name "unconnected-(U4-INT1-Pad8)") (class "Default")
      (node (ref "U4") (pin "8") (pinfunction "INT1_8") (pintype "passive+no_connect"))
    )
    (net (code "144") (name "unconnected-(U4-INT2-Pad9)") (class "Default")
      (node (ref "U4") (pin "9") (pinfunction "INT2_9") (pintype "passive+no_connect"))
    )
    (net (code "145") (name "unconnected-(U4-NC-Pad10)") (class "Default")
      (node (ref "U4") (pin "10") (pinfunction "NC_10") (pintype "passive+no_connect"))
    )
    (net (code "146") (name "unconnected-(U4-NP-Pad3)") (class "Default")
      (node (ref "U4") (pin "3") (pinfunction "NP_3") (pintype "passive+no_connect"))
    )
    (net (code "147") (name "unconnected-(U4-NP-Pad11)") (class "Default")
      (node (ref "U4") (pin "11") (pinfunction "NP_11") (pintype "passive+no_connect"))
    )
    (net (code "148") (name "unconnected-(U5-GND-Pad13)") (class "Default")
      (node (ref "U5") (pin "13") (pinfunction "GND_13") (pintype "passive"))
    )
    (net (code "149") (name "unconnected-(U5-VBAT-Pad14)") (class "Default")
      (node (ref "U5") (pin "14") (pinfunction "VBAT_14") (pintype "passive"))
    )
    (net (code "150") (name "unconnected-(U5-~{IN}T-Pad3)") (class "Default")
      (node (ref "U5") (pin "3") (pinfunction "~{IN}T_3") (pintype "passive+no_connect"))
    )
    (net (code "151") (name "unconnected-(U8-CTS_N-Pad11)") (class "Default")
      (node (ref "U8") (pin "11") (pinfunction "CTS_N_11") (pintype "passive"))
    )
    (net (code "152") (name "unconnected-(U8-DCD_N-Pad10)") (class "Default")
      (node (ref "U8") (pin "10") (pinfunction "DCD_N_10") (pintype "passive"))
    )
    (net (code "153") (name "unconnected-(U8-DSR_N-Pad9)") (class "Default")
      (node (ref "U8") (pin "9") (pinfunction "DSR_N_9") (pintype "passive"))
    )
    (net (code "154") (name "unconnected-(U8-DTR_N-Pad2)") (class "Default")
      (node (ref "U8") (pin "2") (pinfunction "DTR_N_2") (pintype "passive"))
    )
    (net (code "155") (name "unconnected-(U8-NC-Pad8)") (class "Default")
      (node (ref "U8") (pin "8") (pinfunction "NC_8") (pintype "passive"))
    )
    (net (code "156") (name "unconnected-(U8-NC-Pad24)") (class "Default")
      (node (ref "U8") (pin "24") (pinfunction "NC_24") (pintype "passive"))
    )
    (net (code "157") (name "unconnected-(U8-RI_N-Pad6)") (class "Default")
      (node (ref "U8") (pin "6") (pinfunction "RI_N_6") (pintype "passive"))
    )
    (net (code "158") (name "unconnected-(U8-RTS-Pad3)") (class "Default")
      (node (ref "U8") (pin "3") (pinfunction "RTS_3") (pintype "passive"))
    )
    (net (code "159") (name "unconnected-(U8-SHTD_N-Pad12)") (class "Default")
      (node (ref "U8") (pin "12") (pinfunction "SHTD_N_12") (pintype "passive"))
    )
  )
)
